# ES.net
KiCad netlist of a schematic drawn in Altium Designer
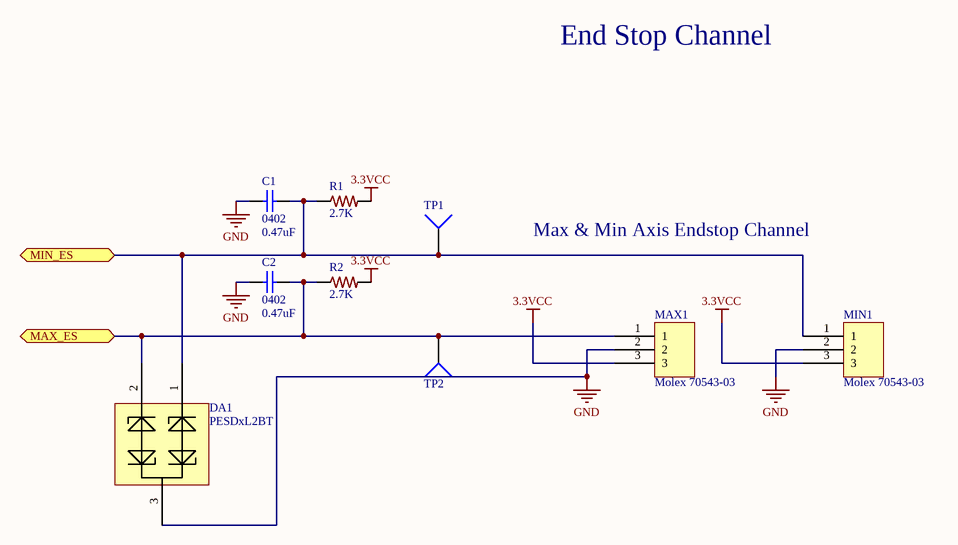
[diagram p0: ES.SchDoc]

(export (version "E")
  (design (tool "Eeschema 10.0.6"))
  (components
    (comp (ref "C1")
      (value "0.47uF")
      (footprint "C0402")
      (description "0.47uF 6.3v C0402 - GRM155R60J474KE19D")
      (fields
        (field (name "MFR PART #") "GRM155R60J474KE19D")
        (field (name "MFR") "Murata")
        (field (name "PACKAGEREFERENCE") "0402")
        (field (name "PUBLISHER") "Ultimachine")
      )
      (libsource (lib "Tigershark3D") (part "GRM155R60J474KE19D"))
    )
    (comp (ref "C2")
      (value "0.47uF")
      (footprint "C0402")
      (description "0.47uF 6.3v C0402 - GRM155R60J474KE19D")
      (fields
        (field (name "MFR PART #") "GRM155R60J474KE19D")
        (field (name "MFR") "Murata")
        (field (name "PACKAGEREFERENCE") "0402")
        (field (name "PUBLISHER") "Ultimachine")
      )
      (libsource (lib "Tigershark3D") (part "GRM155R60J474KE19D"))
    )
    (comp (ref "DA1")
      (value "PESDxL2BT")
      (footprint "SOT95P230X110-3N")
      (description "PESDxL2BT TVS Diode Array 2x")
      (libsource (lib "Tigershark3D") (part "PESDxL2BT"))
    )
    (comp (ref "MAX1")
      (value "Molex 70543-03")
      (footprint "70543-03")
      (libsource (lib "RADMBo Schematic Library") (part "Molex Endstop"))
    )
    (comp (ref "MIN1")
      (value "Molex 70543-03")
      (footprint "70543-03")
      (libsource (lib "RADMBo Schematic Library") (part "Molex Endstop"))
    )
    (comp (ref "R1")
      (value "2.7K")
      (footprint "R0402")
      (description "RES SMD 2.7K OHM 5% 1/10W 0402")
      (fields
        (field (name "MANUFACTURERPARTNUMBER") "ERJ-2GEJ272X")
        (field (name "TOLERANCE") "5%")
        (field (name "PUBLISHER") "Adam Vadala-Roth")
      )
      (libsource (lib "Tigershark3D") (part "ERJ-2GEJ272X"))
    )
    (comp (ref "R2")
      (value "2.7K")
      (footprint "R0402")
      (description "RES SMD 2.7K OHM 5% 1/10W 0402")
      (fields
        (field (name "MANUFACTURERPARTNUMBER") "ERJ-2GEJ272X")
        (field (name "TOLERANCE") "5%")
        (field (name "PUBLISHER") "Adam Vadala-Roth")
      )
      (libsource (lib "Tigershark3D") (part "ERJ-2GEJ272X"))
    )
    (comp (ref "TP1")
      (value "TP4")
      (footprint "TP-2")
      (description "Socket")
      (fields (field (name "PUBLISHER") "Altium Limited"))
      (libsource (lib "ZMBo Schematic Library") (part "Socket"))
    )
    (comp (ref "TP2")
      (value "TP4")
      (footprint "TP-2")
      (description "Socket")
      (fields (field (name "PUBLISHER") "Altium Limited"))
      (libsource (lib "ZMBo Schematic Library") (part "Socket"))
    )
  )
  (nets
    (net (code "1") (name "/MAX_ES") (class "Default")
      (node (ref "C2") (pin "1") (pinfunction "1_1") (pintype "passive"))
      (node (ref "DA1") (pin "2") (pinfunction "2_2") (pintype "passive"))
      (node (ref "MAX1") (pin "1") (pinfunction "1_1") (pintype "passive"))
      (node (ref "R2") (pin "1") (pinfunction "1_1") (pintype "passive"))
      (node (ref "TP2") (pin "1") (pinfunction "1_1") (pintype "passive"))
    )
    (net (code "2") (name "/MIN_ES") (class "Default")
      (node (ref "C1") (pin "1") (pinfunction "1_1") (pintype "passive"))
      (node (ref "DA1") (pin "1") (pinfunction "1_1") (pintype "passive"))
      (node (ref "MIN1") (pin "1") (pinfunction "1_1") (pintype "passive"))
      (node (ref "R1") (pin "1") (pinfunction "1_1") (pintype "passive"))
      (node (ref "TP1") (pin "1") (pinfunction "1_1") (pintype "passive"))
    )
    (net (code "3") (name "3.3VCC") (class "Default")
      (node (ref "MAX1") (pin "3") (pinfunction "3_3") (pintype "passive"))
      (node (ref "MIN1") (pin "3") (pinfunction "3_3") (pintype "passive"))
      (node (ref "R1") (pin "2") (pinfunction "2_2") (pintype "passive"))
      (node (ref "R2") (pin "2") (pinfunction "2_2") (pintype "passive"))
    )
    (net (code "4") (name "GND") (class "Default")
      (node (ref "C1") (pin "2") (pinfunction "2_2") (pintype "passive"))
      (node (ref "C2") (pin "2") (pinfunction "2_2") (pintype "passive"))
      (node (ref "DA1") (pin "3") (pinfunction "3_3") (pintype "passive"))
      (node (ref "MAX1") (pin "2") (pinfunction "2_2") (pintype "passive"))
      (node (ref "MIN1") (pin "2") (pinfunction "2_2") (pintype "passive"))
    )
  )
)
